# Crystal.net
KiCad netlist of a schematic drawn in Altium Designer
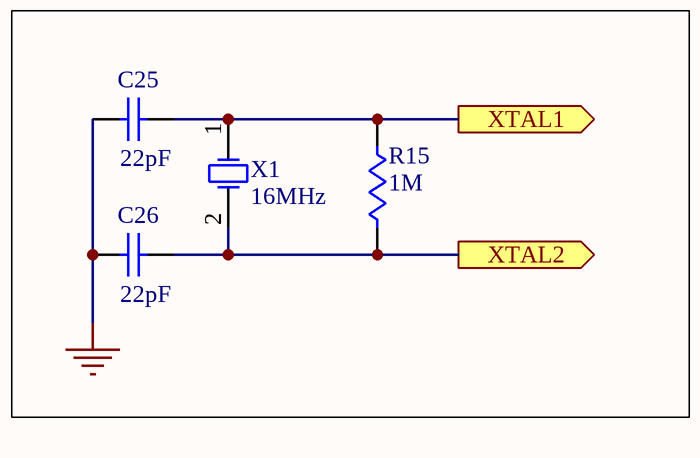
[diagram p0: Crystal.SchDoc]

(export (version "E")
  (design (tool "Eeschema 10.0.6"))
  (components
    (comp (ref "C25")
      (value "22pF")
      (footprint "0805")
      (description "Capacitor")
      (fields (field (name "MANUFACTURER") "Generic Components") (field (name "PUBLISHER") "Altium Limited"))
      (libsource (lib "Miscellaneous Devices") (part "Cap"))
    )
    (comp (ref "C26")
      (value "22pF")
      (footprint "0805")
      (description "Capacitor")
      (fields (field (name "MANUFACTURER") "Generic Components") (field (name "PUBLISHER") "Altium Limited"))
      (libsource (lib "Miscellaneous Devices") (part "Cap"))
    )
    (comp (ref "R15")
      (value "1M")
      (footprint "0805")
      (description "Resistor")
      (fields (field (name "MANUFACTURER") "Generic Components") (field (name "PUBLISHER") "Altium Limited"))
      (libsource (lib "Miscellaneous Devices") (part "Res1"))
    )
    (comp (ref "X1")
      (value "16MHz")
      (footprint "XTAL_2")
      (description "Crystal Oscillator")
      (fields (field (name "MANUFACTURER") "Generic Components") (field (name "PUBLISHER") "Altium Limited"))
      (libsource (lib "Miscellaneous Devices") (part "XTAL"))
    )
  )
  (nets
    (net (code "1") (name "/XTAL1") (class "Default")
      (node (ref "C25") (pin "1") (pinfunction "1_1") (pintype "passive"))
      (node (ref "R15") (pin "2") (pinfunction "2_2") (pintype "passive"))
      (node (ref "X1") (pin "1") (pinfunction "OSC1_1") (pintype "passive"))
    )
    (net (code "2") (name "/XTAL2") (class "Default")
      (node (ref "C26") (pin "1") (pinfunction "1_1") (pintype "passive"))
      (node (ref "R15") (pin "1") (pinfunction "1_1") (pintype "passive"))
      (node (ref "X1") (pin "2") (pinfunction "OSC2_2") (pintype "passive"))
    )
    (net (code "3") (name "GND") (class "Default")
      (node (ref "C25") (pin "2") (pinfunction "2_2") (pintype "passive"))
      (node (ref "C26") (pin "2") (pinfunction "2_2") (pintype "passive"))
    )
  )
)
